# MicroMod-Ethernet-Function-Board-W5500.net
KiCad netlist of a schematic drawn in EAGLE
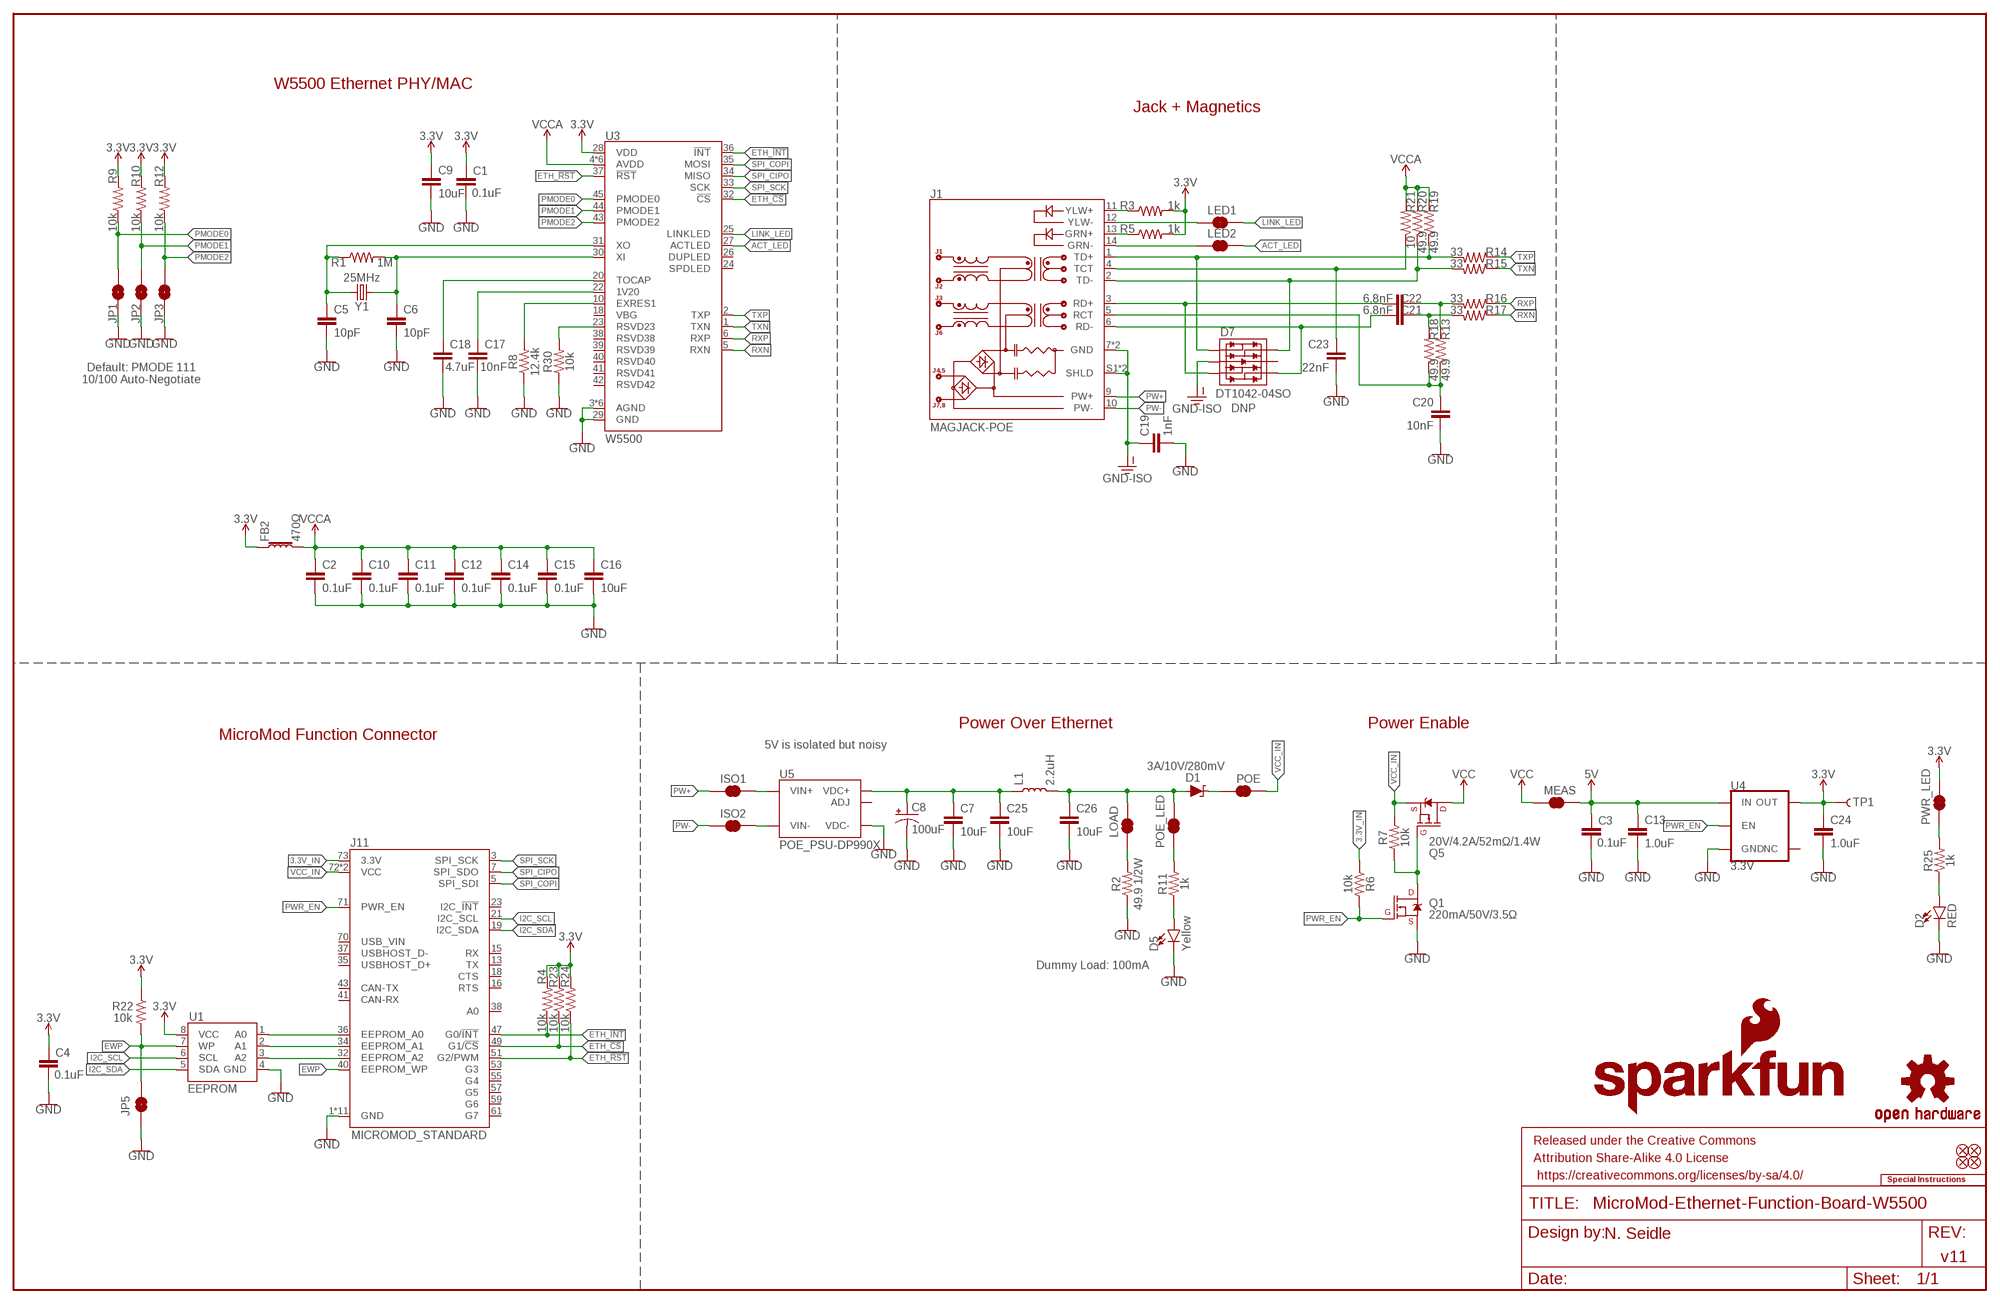
[diagram p0: schematic, sheet 1]

(export (version "E")
  (design (tool "Eeschema 10.0.6"))
  (components
    (comp (ref "C1")
      (value "0.1uF")
      (footprint "eagle-import:0603")
      (libsource (lib "eagle-import") (part "0.1UF-0603-25V-(+80/-20%)"))
    )
    (comp (ref "C2")
      (value "0.1uF")
      (footprint "eagle-import:0603")
      (libsource (lib "eagle-import") (part "0.1UF-0603-25V-5%"))
    )
    (comp (ref "C3")
      (value "0.1uF")
      (footprint "eagle-import:0603")
      (libsource (lib "eagle-import") (part "0.1UF-0603-25V-(+80/-20%)"))
    )
    (comp (ref "C4")
      (value "0.1uF")
      (footprint "eagle-import:0603")
      (libsource (lib "eagle-import") (part "0.1UF-0603-25V-(+80/-20%)"))
    )
    (comp (ref "C5")
      (value "10pF")
      (footprint "eagle-import:0603")
      (libsource (lib "eagle-import") (part "10PF-0603-50V-5%"))
    )
    (comp (ref "C6")
      (value "10pF")
      (footprint "eagle-import:0603")
      (libsource (lib "eagle-import") (part "10PF-0603-50V-5%"))
    )
    (comp (ref "C7")
      (value "10uF")
      (footprint "eagle-import:0805")
      (libsource (lib "eagle-import") (part "10UF-0805-25V-10%"))
    )
    (comp (ref "C8")
      (value "100uF")
      (footprint "eagle-import:PANASONIC_D")
      (libsource (lib "eagle-import") (part "100UF-POLAR-25V-20%(ELEC)"))
    )
    (comp (ref "C9")
      (value "10uF")
      (footprint "eagle-import:0603")
      (libsource (lib "eagle-import") (part "10UF-0603-6.3V-20%"))
    )
    (comp (ref "C10")
      (value "0.1uF")
      (footprint "eagle-import:0603")
      (libsource (lib "eagle-import") (part "0.1UF-0603-25V-5%"))
    )
    (comp (ref "C11")
      (value "0.1uF")
      (footprint "eagle-import:0603")
      (libsource (lib "eagle-import") (part "0.1UF-0603-25V-5%"))
    )
    (comp (ref "C12")
      (value "0.1uF")
      (footprint "eagle-import:0603")
      (libsource (lib "eagle-import") (part "0.1UF-0603-25V-5%"))
    )
    (comp (ref "C13")
      (value "1.0uF")
      (footprint "eagle-import:0603")
      (libsource (lib "eagle-import") (part "1.0UF-0603-16V-10%"))
    )
    (comp (ref "C14")
      (value "0.1uF")
      (footprint "eagle-import:0603")
      (libsource (lib "eagle-import") (part "0.1UF-0603-25V-5%"))
    )
    (comp (ref "C15")
      (value "0.1uF")
      (footprint "eagle-import:0603")
      (libsource (lib "eagle-import") (part "0.1UF-0603-25V-5%"))
    )
    (comp (ref "C16")
      (value "10uF")
      (footprint "eagle-import:0603")
      (libsource (lib "eagle-import") (part "10UF-0603-6.3V-20%"))
    )
    (comp (ref "C17")
      (value "10nF")
      (footprint "eagle-import:0603")
      (libsource (lib "eagle-import") (part "10NF-0603-50V-10%"))
    )
    (comp (ref "C18")
      (value "4.7uF")
      (footprint "eagle-import:0603")
      (libsource (lib "eagle-import") (part "4.7UF-0603-6.3V-(10%)"))
    )
    (comp (ref "C19")
      (value "1nF")
      (footprint "eagle-import:1206")
      (libsource (lib "eagle-import") (part "1.0NF/1000PF-1206-2KV-10%"))
    )
    (comp (ref "C20")
      (value "10nF")
      (footprint "eagle-import:0603")
      (libsource (lib "eagle-import") (part "10NF-0603-50V-10%"))
    )
    (comp (ref "C21")
      (value "6.8nF")
      (footprint "eagle-import:0603")
      (libsource (lib "eagle-import") (part "6.8NF/6800PF-0603-50V-5%"))
    )
    (comp (ref "C22")
      (value "6.8nF")
      (footprint "eagle-import:0603")
      (libsource (lib "eagle-import") (part "6.8NF/6800PF-0603-50V-5%"))
    )
    (comp (ref "C23")
      (value "22nF")
      (footprint "eagle-import:0603")
      (libsource (lib "eagle-import") (part "22NF/22,000PF-0603-50V-10%"))
    )
    (comp (ref "C24")
      (value "1.0uF")
      (footprint "eagle-import:0603")
      (libsource (lib "eagle-import") (part "1.0UF-0603-16V-10%-X7R"))
    )
    (comp (ref "C25")
      (value "10uF")
      (footprint "eagle-import:0805")
      (libsource (lib "eagle-import") (part "10UF-0805-25V-10%"))
    )
    (comp (ref "C26")
      (value "10uF")
      (footprint "eagle-import:0805")
      (libsource (lib "eagle-import") (part "10UF-0805-25V-10%"))
    )
    (comp (ref "D1")
      (value "3A/10V/280mV")
      (footprint "eagle-import:SOD-323")
      (libsource (lib "eagle-import") (part "DIODE-SCHOTTKY-BAT60A"))
    )
    (comp (ref "D2")
      (value "RED")
      (footprint "eagle-import:LED-0603")
      (libsource (lib "eagle-import") (part "LED-RED0603"))
    )
    (comp (ref "D5")
      (value "Yellow")
      (footprint "eagle-import:LED-0603")
      (libsource (lib "eagle-import") (part "LED-YELLOW0603"))
    )
    (comp (ref "D7")
      (value "DT1042-04SO")
      (footprint "eagle-import:SOT-23-6")
      (libsource (lib "eagle-import") (part "TVS_DIODE_ARRAYSMD"))
    )
    (comp (ref "FB2")
      (value "470Ω")
      (footprint "eagle-import:0603")
      (libsource (lib "eagle-import") (part "FERRITE_BEAD-0603-470Ω-100MHZ-1A-200MILIΩ"))
    )
    (comp (ref "FD1")
      (value "FIDUCIALUFIDUCIAL")
      (footprint "eagle-import:FIDUCIAL-MICRO")
      (libsource (lib "eagle-import") (part "FIDUCIALUFIDUCIAL"))
    )
    (comp (ref "FD2")
      (value "FIDUCIALUFIDUCIAL")
      (footprint "eagle-import:FIDUCIAL-MICRO")
      (libsource (lib "eagle-import") (part "FIDUCIALUFIDUCIAL"))
    )
    (comp (ref "FD3")
      (value "FIDUCIALUFIDUCIAL")
      (footprint "eagle-import:FIDUCIAL-MICRO")
      (libsource (lib "eagle-import") (part "FIDUCIALUFIDUCIAL"))
    )
    (comp (ref "FD4")
      (value "FIDUCIALUFIDUCIAL")
      (footprint "eagle-import:FIDUCIAL-MICRO")
      (libsource (lib "eagle-import") (part "FIDUCIALUFIDUCIAL"))
    )
    (comp (ref "FRAME1")
      (value "FRAME-LEDGER")
      (footprint "eagle-import:CREATIVE_COMMONS")
      (libsource (lib "eagle-import") (part "FRAME-LEDGER"))
    )
    (comp (ref "ISO1")
      (value "JUMPER-COMBO_2_NC_TRACE")
      (footprint "eagle-import:COMBO-JUMPER_2_NC_TRACE")
      (libsource (lib "eagle-import") (part "JUMPER-COMBO_2_NC_TRACE"))
    )
    (comp (ref "ISO2")
      (value "JUMPER-COMBO_2_NC_TRACE")
      (footprint "eagle-import:COMBO-JUMPER_2_NC_TRACE")
      (libsource (lib "eagle-import") (part "JUMPER-COMBO_2_NC_TRACE"))
    )
    (comp (ref "J1")
      (value "MAGJACK-POE")
      (footprint "eagle-import:MAGJACK-SYM_LED")
      (libsource (lib "eagle-import") (part "MAGJACK-POE"))
    )
    (comp (ref "J11")
      (value "MICROMOD_STANDARD")
      (footprint "eagle-import:M.2-CARD-E-22_FUNCTION_STANDARD")
      (libsource (lib "eagle-import") (part "MICROMOD_STANDARD"))
    )
    (comp (ref "JP1")
      (value "JUMPER-SMT_2_NO_SILK")
      (footprint "eagle-import:SMT-JUMPER_2_NO_SILK")
      (libsource (lib "eagle-import") (part "JUMPER-SMT_2_NO_SILK"))
    )
    (comp (ref "JP2")
      (value "JUMPER-SMT_2_NO_SILK")
      (footprint "eagle-import:SMT-JUMPER_2_NO_SILK")
      (libsource (lib "eagle-import") (part "JUMPER-SMT_2_NO_SILK"))
    )
    (comp (ref "JP3")
      (value "JUMPER-SMT_2_NO_SILK")
      (footprint "eagle-import:SMT-JUMPER_2_NO_SILK")
      (libsource (lib "eagle-import") (part "JUMPER-SMT_2_NO_SILK"))
    )
    (comp (ref "JP5")
      (value "JUMPER-SMT_2_NO_SILK")
      (footprint "eagle-import:SMT-JUMPER_2_NO_SILK")
      (libsource (lib "eagle-import") (part "JUMPER-SMT_2_NO_SILK"))
    )
    (comp (ref "L1")
      (value "2.2uH")
      (footprint "eagle-import:0805-WIDE")
      (libsource (lib "eagle-import") (part "INDUCTOR-0805_WIDE-2.2UH"))
    )
    (comp (ref "LED1")
      (value "JUMPER-SMT_2_NC_TRACE_SILK")
      (footprint "eagle-import:SMT-JUMPER_2_NC_TRACE_SILK")
      (libsource (lib "eagle-import") (part "JUMPER-SMT_2_NC_TRACE_SILK"))
    )
    (comp (ref "LED2")
      (value "JUMPER-SMT_2_NC_TRACE_SILK")
      (footprint "eagle-import:SMT-JUMPER_2_NC_TRACE_SILK")
      (libsource (lib "eagle-import") (part "JUMPER-SMT_2_NC_TRACE_SILK"))
    )
    (comp (ref "LOAD")
      (value "JUMPER-SMT_2_NC_TRACE_SILK")
      (footprint "eagle-import:SMT-JUMPER_2_NC_TRACE_SILK")
      (libsource (lib "eagle-import") (part "JUMPER-SMT_2_NC_TRACE_SILK"))
    )
    (comp (ref "LOGO1")
      (value "SFE_LOGO_NAME_FLAME.1_INCH")
      (footprint "eagle-import:SFE_LOGO_NAME_FLAME_.1")
      (libsource (lib "eagle-import") (part "SFE_LOGO_NAME_FLAME.1_INCH"))
    )
    (comp (ref "LOGO2")
      (value "SPECIAL_INSTRUCTIONS-ORDERING")
      (footprint "eagle-import:ORDERING_INSTRUCTIONS")
      (libsource (lib "eagle-import") (part "SPECIAL_INSTRUCTIONS-ORDERING"))
    )
    (comp (ref "LOGO3")
      (value "OSHW-LOGOMINI")
      (footprint "eagle-import:OSHW-LOGO-MINI")
      (libsource (lib "eagle-import") (part "OSHW-LOGOMINI"))
    )
    (comp (ref "MEAS")
      (value "JUMPER-COMBO_2_NC_TRACE")
      (footprint "eagle-import:COMBO-JUMPER_2_NC_TRACE")
      (libsource (lib "eagle-import") (part "JUMPER-COMBO_2_NC_TRACE"))
    )
    (comp (ref "POE")
      (value "JUMPER-SMT_2_NC_TRACE_SILK")
      (footprint "eagle-import:SMT-JUMPER_2_NC_TRACE_SILK")
      (libsource (lib "eagle-import") (part "JUMPER-SMT_2_NC_TRACE_SILK"))
    )
    (comp (ref "POE_LED")
      (value "JUMPER-SMT_2_NC_TRACE_SILK")
      (footprint "eagle-import:SMT-JUMPER_2_NC_TRACE_SILK")
      (libsource (lib "eagle-import") (part "JUMPER-SMT_2_NC_TRACE_SILK"))
    )
    (comp (ref "PWR_LED")
      (value "JUMPER-SMT_2_NC_TRACE_SILK")
      (footprint "eagle-import:SMT-JUMPER_2_NC_TRACE_SILK")
      (libsource (lib "eagle-import") (part "JUMPER-SMT_2_NC_TRACE_SILK"))
    )
    (comp (ref "Q1")
      (value "220mA/50V/3.5Ω")
      (footprint "eagle-import:SOT23-3")
      (libsource (lib "eagle-import") (part "MOSFET-NCH-BSS138"))
    )
    (comp (ref "Q5")
      (value "20V/4.2A/52mΩ/1.4W")
      (footprint "eagle-import:SOT23-3")
      (libsource (lib "eagle-import") (part "MOSFET_PCH-DMG2305UX-7"))
    )
    (comp (ref "R1")
      (value "1M")
      (footprint "eagle-import:0603")
      (libsource (lib "eagle-import") (part "1MOHM-0603-1/4W-5%"))
    )
    (comp (ref "R2")
      (value "49.9 1/2W")
      (footprint "eagle-import:1206")
      (libsource (lib "eagle-import") (part "49.9OHM-1206-1/2W-1%"))
    )
    (comp (ref "R3")
      (value "1k")
      (footprint "eagle-import:0603")
      (libsource (lib "eagle-import") (part "1KOHM-0603-1/10W-1%"))
    )
    (comp (ref "R4")
      (value "10k")
      (footprint "eagle-import:0603")
      (libsource (lib "eagle-import") (part "10KOHM-0603-1/10W-1%"))
    )
    (comp (ref "R5")
      (value "1k")
      (footprint "eagle-import:0603")
      (libsource (lib "eagle-import") (part "1KOHM-0603-1/10W-1%"))
    )
    (comp (ref "R6")
      (value "10k")
      (footprint "eagle-import:0603")
      (libsource (lib "eagle-import") (part "10KOHM-0603-1/10W-1%"))
    )
    (comp (ref "R7")
      (value "10k")
      (footprint "eagle-import:0603")
      (libsource (lib "eagle-import") (part "10KOHM-0603-1/10W-1%"))
    )
    (comp (ref "R8")
      (value "12.4k")
      (footprint "eagle-import:0603")
      (libsource (lib "eagle-import") (part "12.4KOHM-0603-1/10W-1%"))
    )
    (comp (ref "R9")
      (value "10k")
      (footprint "eagle-import:0603")
      (libsource (lib "eagle-import") (part "10KOHM-0603-1/10W-1%"))
    )
    (comp (ref "R10")
      (value "10k")
      (footprint "eagle-import:0603")
      (libsource (lib "eagle-import") (part "10KOHM-0603-1/10W-1%"))
    )
    (comp (ref "R11")
      (value "1k")
      (footprint "eagle-import:0603")
      (libsource (lib "eagle-import") (part "1KOHM-0603-1/10W-1%"))
    )
    (comp (ref "R12")
      (value "10k")
      (footprint "eagle-import:0603")
      (libsource (lib "eagle-import") (part "10KOHM-0603-1/10W-1%"))
    )
    (comp (ref "R13")
      (value "49.9")
      (footprint "eagle-import:0603")
      (libsource (lib "eagle-import") (part "49.9OHM-0603-1/10W-1%"))
    )
    (comp (ref "R14")
      (value "33")
      (footprint "eagle-import:0603")
      (libsource (lib "eagle-import") (part "33OHM-0603-1/10W-1%"))
    )
    (comp (ref "R15")
      (value "33")
      (footprint "eagle-import:0603")
      (libsource (lib "eagle-import") (part "33OHM-0603-1/10W-1%"))
    )
    (comp (ref "R16")
      (value "33")
      (footprint "eagle-import:0603")
      (libsource (lib "eagle-import") (part "33OHM-0603-1/10W-1%"))
    )
    (comp (ref "R17")
      (value "33")
      (footprint "eagle-import:0603")
      (libsource (lib "eagle-import") (part "33OHM-0603-1/10W-1%"))
    )
    (comp (ref "R18")
      (value "49.9")
      (footprint "eagle-import:0603")
      (libsource (lib "eagle-import") (part "49.9OHM-0603-1/10W-1%"))
    )
    (comp (ref "R19")
      (value "49.9")
      (footprint "eagle-import:0603")
      (libsource (lib "eagle-import") (part "49.9OHM-0603-1/10W-1%"))
    )
    (comp (ref "R20")
      (value "49.9")
      (footprint "eagle-import:0603")
      (libsource (lib "eagle-import") (part "49.9OHM-0603-1/10W-1%"))
    )
    (comp (ref "R21")
      (value "10")
      (footprint "eagle-import:0603")
      (libsource (lib "eagle-import") (part "10OHM-0603-1/10W-1%"))
    )
    (comp (ref "R22")
      (value "10k")
      (footprint "eagle-import:0603")
      (libsource (lib "eagle-import") (part "10KOHM-0603-1/10W-1%"))
    )
    (comp (ref "R23")
      (value "10k")
      (footprint "eagle-import:0603")
      (libsource (lib "eagle-import") (part "10KOHM-0603-1/10W-1%"))
    )
    (comp (ref "R24")
      (value "10k")
      (footprint "eagle-import:0603")
      (libsource (lib "eagle-import") (part "10KOHM-0603-1/10W-1%"))
    )
    (comp (ref "R25")
      (value "1k")
      (footprint "eagle-import:0603")
      (libsource (lib "eagle-import") (part "1KOHM-0603-1/10W-1%"))
    )
    (comp (ref "R30")
      (value "10k")
      (footprint "eagle-import:0603")
      (libsource (lib "eagle-import") (part "10KOHM-0603-1/10W-1%"))
    )
    (comp (ref "TP1")
      (value "TEST-POINT3X4")
      (footprint "eagle-import:PAD.03X.04")
      (libsource (lib "eagle-import") (part "TEST-POINT3X4"))
    )
    (comp (ref "U1")
      (value "EEPROM")
      (footprint "eagle-import:SO08")
      (libsource (lib "eagle-import") (part "EEPROM-I2C512K"))
    )
    (comp (ref "U3")
      (value "W5500")
      (footprint "eagle-import:LQFP-48")
      (libsource (lib "eagle-import") (part "W5500"))
    )
    (comp (ref "U4")
      (value "3.3V")
      (footprint "eagle-import:SOT23-5")
      (libsource (lib "eagle-import") (part "V_REG_AP2112K-3.3V"))
    )
    (comp (ref "U5")
      (value "POE_PSU-DP990X")
      (footprint "eagle-import:DP990X")
      (libsource (lib "eagle-import") (part "POE_PSU-DP990X"))
    )
    (comp (ref "Y1")
      (value "25MHz")
      (footprint "eagle-import:CRYSTAL-SMD-2.0X1.6MM")
      (libsource (lib "eagle-import") (part "CRYSTAL-25MHZ-SMD-2.0X1.6MM"))
    )
  )
  (nets
    (net (code "1") (name "/ETH_~{CS}") (class "Default")
      (node (ref "J11") (pin "49") (pinfunction "G1/~{CS}_49") (pintype "bidirectional"))
      (node (ref "R23") (pin "1") (pinfunction "1_1") (pintype "passive"))
      (node (ref "U3") (pin "32") (pinfunction "~{CS}_32") (pintype "bidirectional"))
    )
    (net (code "2") (name "/ETH_~{INT}") (class "Default")
      (node (ref "J11") (pin "47") (pinfunction "G0/~{INT}_47") (pintype "bidirectional"))
      (node (ref "R4") (pin "1") (pinfunction "1_1") (pintype "passive"))
      (node (ref "U3") (pin "36") (pinfunction "~{INT}_36") (pintype "bidirectional"))
    )
    (net (code "3") (name "/ETH_~{RST}") (class "Default")
      (node (ref "J11") (pin "51") (pinfunction "G2/PWM_51") (pintype "bidirectional"))
      (node (ref "R24") (pin "1") (pinfunction "1_1") (pintype "passive"))
      (node (ref "U3") (pin "37") (pinfunction "~{RST}_37") (pintype "bidirectional"))
    )
    (net (code "4") (name "3.3V") (class "Default")
      (node (ref "C1") (pin "1") (pinfunction "1_1") (pintype "passive"))
      (node (ref "C24") (pin "1") (pinfunction "1_1") (pintype "passive"))
      (node (ref "C4") (pin "1") (pinfunction "1_1") (pintype "passive"))
      (node (ref "C9") (pin "1") (pinfunction "1_1") (pintype "passive"))
      (node (ref "FB2") (pin "1") (pinfunction "1_1") (pintype "passive"))
      (node (ref "PWR_LED") (pin "2") (pinfunction "2_2") (pintype "passive"))
      (node (ref "R10") (pin "2") (pinfunction "2_2") (pintype "passive"))
      (node (ref "R12") (pin "2") (pinfunction "2_2") (pintype "passive"))
      (node (ref "R22") (pin "1") (pinfunction "1_1") (pintype "passive"))
      (node (ref "R23") (pin "2") (pinfunction "2_2") (pintype "passive"))
      (node (ref "R24") (pin "2") (pinfunction "2_2") (pintype "passive"))
      (node (ref "R3") (pin "2") (pinfunction "2_2") (pintype "passive"))
      (node (ref "R4") (pin "2") (pinfunction "2_2") (pintype "passive"))
      (node (ref "R5") (pin "2") (pinfunction "2_2") (pintype "passive"))
      (node (ref "R9") (pin "2") (pinfunction "2_2") (pintype "passive"))
      (node (ref "TP1") (pin "1") (pinfunction "1_1") (pintype "bidirectional"))
      (node (ref "U1") (pin "8") (pinfunction "VCC_8") (pintype "power_in"))
      (node (ref "U3") (pin "28") (pinfunction "VDD_28") (pintype "bidirectional"))
      (node (ref "U4") (pin "5") (pinfunction "OUT_5") (pintype "passive"))
    )
    (net (code "5") (name "3.3V_IN") (class "Default")
      (node (ref "J11") (pin "73") (pinfunction "3.3V_73") (pintype "bidirectional"))
      (node (ref "R6") (pin "1") (pinfunction "1_1") (pintype "passive"))
    )
    (net (code "6") (name "5V") (class "Default")
      (node (ref "C13") (pin "1") (pinfunction "1_1") (pintype "passive"))
      (node (ref "C3") (pin "1") (pinfunction "1_1") (pintype "passive"))
      (node (ref "MEAS") (pin "2") (pinfunction "2_2") (pintype "passive"))
      (node (ref "MEAS") (pin "4") (pinfunction "2_4") (pintype "passive"))
      (node (ref "U4") (pin "1") (pinfunction "IN_1") (pintype "input"))
    )
    (net (code "7") (name "ACT_LED") (class "Default")
      (node (ref "LED2") (pin "2") (pinfunction "2_2") (pintype "passive"))
      (node (ref "U3") (pin "27") (pinfunction "ACTLED_27") (pintype "bidirectional"))
    )
    (net (code "8") (name "EWP") (class "Default")
      (node (ref "J11") (pin "40") (pinfunction "EEPROM_WP_40") (pintype "bidirectional"))
      (node (ref "JP5") (pin "2") (pinfunction "2_2") (pintype "passive"))
      (node (ref "R22") (pin "2") (pinfunction "2_2") (pintype "passive"))
      (node (ref "U1") (pin "7") (pinfunction "WP_7") (pintype "bidirectional"))
    )
    (net (code "9") (name "GND") (class "Default")
      (node (ref "C1") (pin "2") (pinfunction "2_2") (pintype "passive"))
      (node (ref "C10") (pin "2") (pinfunction "2_2") (pintype "passive"))
      (node (ref "C11") (pin "2") (pinfunction "2_2") (pintype "passive"))
      (node (ref "C12") (pin "2") (pinfunction "2_2") (pintype "passive"))
      (node (ref "C13") (pin "2") (pinfunction "2_2") (pintype "passive"))
      (node (ref "C14") (pin "2") (pinfunction "2_2") (pintype "passive"))
      (node (ref "C15") (pin "2") (pinfunction "2_2") (pintype "passive"))
      (node (ref "C16") (pin "2") (pinfunction "2_2") (pintype "passive"))
      (node (ref "C17") (pin "2") (pinfunction "2_2") (pintype "passive"))
      (node (ref "C18") (pin "2") (pinfunction "2_2") (pintype "passive"))
      (node (ref "C19") (pin "2") (pinfunction "2_2") (pintype "passive"))
      (node (ref "C2") (pin "2") (pinfunction "2_2") (pintype "passive"))
      (node (ref "C20") (pin "2") (pinfunction "2_2") (pintype "passive"))
      (node (ref "C23") (pin "2") (pinfunction "2_2") (pintype "passive"))
      (node (ref "C24") (pin "2") (pinfunction "2_2") (pintype "passive"))
      (node (ref "C25") (pin "2") (pinfunction "2_2") (pintype "passive"))
      (node (ref "C26") (pin "2") (pinfunction "2_2") (pintype "passive"))
      (node (ref "C3") (pin "2") (pinfunction "2_2") (pintype "passive"))
      (node (ref "C4") (pin "2") (pinfunction "2_2") (pintype "passive"))
      (node (ref "C5") (pin "2") (pinfunction "2_2") (pintype "passive"))
      (node (ref "C6") (pin "2") (pinfunction "2_2") (pintype "passive"))
      (node (ref "C7") (pin "2") (pinfunction "2_2") (pintype "passive"))
      (node (ref "C8") (pin "-") (pinfunction "-_-") (pintype "passive"))
      (node (ref "C9") (pin "2") (pinfunction "2_2") (pintype "passive"))
      (node (ref "D2") (pin "C") (pinfunction "C_C") (pintype "passive"))
      (node (ref "D5") (pin "C") (pinfunction "C_C") (pintype "passive"))
      (node (ref "J11") (pin "1") (pinfunction "GND_1") (pintype "bidirectional"))
      (node (ref "J11") (pin "33") (pinfunction "GND_33") (pintype "bidirectional"))
      (node (ref "J11") (pin "39") (pinfunction "GND_39") (pintype "bidirectional"))
      (node (ref "J11") (pin "45") (pinfunction "GND_45") (pintype "bidirectional"))
      (node (ref "J11") (pin "75") (pinfunction "GND_75") (pintype "bidirectional"))
      (node (ref "J11") (pin "GND1") (pinfunction "GND_GND1") (pintype "bidirectional"))
      (node (ref "J11") (pin "GND2") (pinfunction "GND_GND2") (pintype "bidirectional"))
      (node (ref "J11") (pin "GND3") (pinfunction "GND_GND3") (pintype "bidirectional"))
      (node (ref "J11") (pin "GND4") (pinfunction "GND_GND4") (pintype "bidirectional"))
      (node (ref "J11") (pin "GND5") (pinfunction "GND_GND5") (pintype "bidirectional"))
      (node (ref "J11") (pin "GND6") (pinfunction "GND_GND6") (pintype "bidirectional"))
      (node (ref "JP1") (pin "1") (pinfunction "1_1") (pintype "passive"))
      (node (ref "JP2") (pin "1") (pinfunction "1_1") (pintype "passive"))
      (node (ref "JP3") (pin "1") (pinfunction "1_1") (pintype "passive"))
      (node (ref "JP5") (pin "1") (pinfunction "1_1") (pintype "passive"))
      (node (ref "Q1") (pin "2") (pinfunction "S_2") (pintype "bidirectional"))
      (node (ref "R2") (pin "1") (pinfunction "1_1") (pintype "passive"))
      (node (ref "R30") (pin "1") (pinfunction "1_1") (pintype "passive"))
      (node (ref "R8") (pin "1") (pinfunction "1_1") (pintype "passive"))
      (node (ref "U1") (pin "4") (pinfunction "GND_4") (pintype "power_in"))
      (node (ref "U3") (pin "14") (pinfunction "AGND_14") (pintype "bidirectional"))
      (node (ref "U3") (pin "16") (pinfunction "AGND_16") (pintype "bidirectional"))
      (node (ref "U3") (pin "19") (pinfunction "AGND_19") (pintype "bidirectional"))
      (node (ref "U3") (pin "29") (pinfunction "GND_29") (pintype "bidirectional"))
      (node (ref "U3") (pin "3") (pinfunction "AGND_3") (pintype "bidirectional"))
      (node (ref "U3") (pin "48") (pinfunction "AGND_48") (pintype "bidirectional"))
      (node (ref "U3") (pin "9") (pinfunction "AGND_9") (pintype "bidirectional"))
      (node (ref "U4") (pin "2") (pinfunction "GND_2") (pintype "input"))
      (node (ref "U5") (pin "3") (pinfunction "VDC-_3") (pintype "bidirectional"))
    )
    (net (code "10") (name "GND-ISO") (class "Default")
      (node (ref "C19") (pin "1") (pinfunction "1_1") (pintype "passive"))
      (node (ref "D7") (pin "2") (pinfunction "VSS_2") (pintype "bidirectional"))
      (node (ref "J1") (pin "7") (pinfunction "GND_7") (pintype "bidirectional"))
      (node (ref "J1") (pin "8") (pinfunction "GND_8") (pintype "bidirectional"))
      (node (ref "J1") (pin "S1") (pinfunction "SHLD_S1") (pintype "bidirectional"))
      (node (ref "J1") (pin "S2") (pinfunction "SHLD_S2") (pintype "bidirectional"))
    )
    (net (code "11") (name "I2C_SCL") (class "Default")
      (node (ref "J11") (pin "21") (pinfunction "I2C_SCL_21") (pintype "bidirectional"))
      (node (ref "U1") (pin "6") (pinfunction "SCL_6") (pintype "bidirectional"))
    )
    (net (code "12") (name "I2C_SDA") (class "Default")
      (node (ref "J11") (pin "19") (pinfunction "I2C_SDA_19") (pintype "bidirectional"))
      (node (ref "U1") (pin "5") (pinfunction "SDA_5") (pintype "bidirectional"))
    )
    (net (code "13") (name "LINK_LED") (class "Default")
      (node (ref "LED1") (pin "2") (pinfunction "2_2") (pintype "passive"))
      (node (ref "U3") (pin "25") (pinfunction "LINKLED_25") (pintype "bidirectional"))
    )
    (net (code "14") (name "Net-(C21-Pad1)") (class "Default")
      (node (ref "C21") (pin "1") (pinfunction "1_1") (pintype "passive"))
      (node (ref "R17") (pin "2") (pinfunction "2_2") (pintype "passive"))
      (node (ref "R18") (pin "2") (pinfunction "2_2") (pintype "passive"))
    )
    (net (code "15") (name "Net-(C22-Pad1)") (class "Default")
      (node (ref "C22") (pin "1") (pinfunction "1_1") (pintype "passive"))
      (node (ref "R13") (pin "2") (pinfunction "2_2") (pintype "passive"))
      (node (ref "R16") (pin "2") (pinfunction "2_2") (pintype "passive"))
    )
    (net (code "16") (name "Net-(C25-Pad1)") (class "Default")
      (node (ref "C25") (pin "1") (pinfunction "1_1") (pintype "passive"))
      (node (ref "C7") (pin "1") (pinfunction "1_1") (pintype "passive"))
      (node (ref "C8") (pin "+") (pinfunction "+_+") (pintype "passive"))
      (node (ref "L1") (pin "1") (pinfunction "1_1") (pintype "passive"))
      (node (ref "U5") (pin "1") (pinfunction "VDC+_1") (pintype "bidirectional"))
      (node (ref "U5") (pin "2") (pinfunction "VDC+_2") (pintype "bidirectional"))
    )
    (net (code "17") (name "Net-(C26-Pad1)") (class "Default")
      (node (ref "C26") (pin "1") (pinfunction "1_1") (pintype "passive"))
      (node (ref "D1") (pin "A") (pinfunction "A_A") (pintype "passive"))
      (node (ref "L1") (pin "2") (pinfunction "2_2") (pintype "passive"))
      (node (ref "LOAD") (pin "2") (pinfunction "2_2") (pintype "passive"))
      (node (ref "POE_LED") (pin "2") (pinfunction "2_2") (pintype "passive"))
    )
    (net (code "18") (name "Net-(D1-PadC)") (class "Default")
      (node (ref "D1") (pin "C") (pinfunction "C_C") (pintype "passive"))
      (node (ref "POE") (pin "1") (pinfunction "1_1") (pintype "passive"))
    )
    (net (code "19") (name "Net-(D2-PadA)") (class "Default")
      (node (ref "D2") (pin "A") (pinfunction "A_A") (pintype "passive"))
      (node (ref "R25") (pin "1") (pinfunction "1_1") (pintype "passive"))
    )
    (net (code "20") (name "Net-(D5-PadA)") (class "Default")
      (node (ref "D5") (pin "A") (pinfunction "A_A") (pintype "passive"))
      (node (ref "R11") (pin "1") (pinfunction "1_1") (pintype "passive"))
    )
    (net (code "21") (name "Net-(D7-IO1)") (class "Default")
      (node (ref "D7") (pin "1") (pinfunction "IO1_1") (pintype "bidirectional"))
      (node (ref "J1") (pin "1") (pinfunction "TD+_1") (pintype "bidirectional"))
      (node (ref "R14") (pin "2") (pinfunction "2_2") (pintype "passive"))
      (node (ref "R19") (pin "1") (pinfunction "1_1") (pintype "passive"))
    )
    (net (code "22") (name "Net-(D7-IO2)") (class "Default")
      (node (ref "C22") (pin "2") (pinfunction "2_2") (pintype "passive"))
      (node (ref "D7") (pin "3") (pinfunction "IO2_3") (pintype "bidirectional"))
      (node (ref "J1") (pin "3") (pinfunction "RD+_3") (pintype "bidirectional"))
    )
    (net (code "23") (name "Net-(D7-IO3)") (class "Default")
      (node (ref "C21") (pin "2") (pinfunction "2_2") (pintype "passive"))
      (node (ref "D7") (pin "4") (pinfunction "IO3_4") (pintype "bidirectional"))
      (node (ref "J1") (pin "6") (pinfunction "RD-_6") (pintype "bidirectional"))
    )
    (net (code "24") (name "Net-(D7-IO4)") (class "Default")
      (node (ref "D7") (pin "6") (pinfunction "IO4_6") (pintype "bidirectional"))
      (node (ref "J1") (pin "2") (pinfunction "TD-_2") (pintype "bidirectional"))
      (node (ref "R15") (pin "2") (pinfunction "2_2") (pintype "passive"))
      (node (ref "R20") (pin "1") (pinfunction "1_1") (pintype "passive"))
    )
    (net (code "25") (name "Net-(ISO1-2-Pad4)") (class "Default")
      (node (ref "ISO1") (pin "2") (pinfunction "2_2") (pintype "passive"))
      (node (ref "ISO1") (pin "4") (pinfunction "2_4") (pintype "passive"))
      (node (ref "U5") (pin "5") (pinfunction "VIN+_5") (pintype "bidirectional"))
      (node (ref "U5") (pin "6") (pinfunction "VIN+_6") (pintype "bidirectional"))
    )
    (net (code "26") (name "Net-(ISO2-2-Pad4)") (class "Default")
      (node (ref "ISO2") (pin "2") (pinfunction "2_2") (pintype "passive"))
      (node (ref "ISO2") (pin "4") (pinfunction "2_4") (pintype "passive"))
      (node (ref "U5") (pin "7") (pinfunction "VIN-_7") (pintype "bidirectional"))
      (node (ref "U5") (pin "8") (pinfunction "VIN-_8") (pintype "bidirectional"))
    )
    (net (code "27") (name "Net-(J1-GRN+)") (class "Default")
      (node (ref "J1") (pin "13") (pinfunction "GRN+_13") (pintype "bidirectional"))
      (node (ref "R5") (pin "1") (pinfunction "1_1") (pintype "passive"))
    )
    (net (code "28") (name "Net-(J1-GRN-)") (class "Default")
      (node (ref "J1") (pin "14") (pinfunction "GRN-_14") (pintype "bidirectional"))
      (node (ref "LED2") (pin "1") (pinfunction "1_1") (pintype "passive"))
    )
    (net (code "29") (name "Net-(J1-RCT)") (class "Default")
      (node (ref "C20") (pin "1") (pinfunction "1_1") (pintype "passive"))
      (node (ref "J1") (pin "5") (pinfunction "RCT_5") (pintype "bidirectional"))
      (node (ref "R13") (pin "1") (pinfunction "1_1") (pintype "passive"))
      (node (ref "R18") (pin "1") (pinfunction "1_1") (pintype "passive"))
    )
    (net (code "30") (name "Net-(J1-TCT)") (class "Default")
      (node (ref "C23") (pin "1") (pinfunction "1_1") (pintype "passive"))
      (node (ref "J1") (pin "4") (pinfunction "TCT_4") (pintype "bidirectional"))
      (node (ref "R21") (pin "1") (pinfunction "1_1") (pintype "passive"))
    )
    (net (code "31") (name "Net-(J1-YLW+)") (class "Default")
      (node (ref "J1") (pin "11") (pinfunction "YLW+_11") (pintype "bidirectional"))
      (node (ref "R3") (pin "1") (pinfunction "1_1") (pintype "passive"))
    )
    (net (code "32") (name "Net-(J1-YLW-)") (class "Default")
      (node (ref "J1") (pin "12") (pinfunction "YLW-_12") (pintype "bidirectional"))
      (node (ref "LED1") (pin "1") (pinfunction "1_1") (pintype "passive"))
    )
    (net (code "33") (name "Net-(J11-EEPROM_A0)") (class "Default")
      (node (ref "J11") (pin "36") (pinfunction "EEPROM_A0_36") (pintype "bidirectional"))
      (node (ref "U1") (pin "1") (pinfunction "A0_1") (pintype "bidirectional"))
    )
    (net (code "34") (name "Net-(J11-EEPROM_A1)") (class "Default")
      (node (ref "J11") (pin "34") (pinfunction "EEPROM_A1_34") (pintype "bidirectional"))
      (node (ref "U1") (pin "2") (pinfunction "A1_2") (pintype "bidirectional"))
    )
    (net (code "35") (name "Net-(J11-EEPROM_A2)") (class "Default")
      (node (ref "J11") (pin "32") (pinfunction "EEPROM_A2_32") (pintype "bidirectional"))
      (node (ref "U1") (pin "3") (pinfunction "A2_3") (pintype "bidirectional"))
    )
    (net (code "36") (name "Net-(LOAD-Pad1)") (class "Default")
      (node (ref "LOAD") (pin "1") (pinfunction "1_1") (pintype "passive"))
      (node (ref "R2") (pin "2") (pinfunction "2_2") (pintype "passive"))
    )
    (net (code "37") (name "Net-(POE_LED-Pad1)") (class "Default")
      (node (ref "POE_LED") (pin "1") (pinfunction "1_1") (pintype "passive"))
      (node (ref "R11") (pin "2") (pinfunction "2_2") (pintype "passive"))
    )
    (net (code "38") (name "Net-(PWR_LED-Pad1)") (class "Default")
      (node (ref "PWR_LED") (pin "1") (pinfunction "1_1") (pintype "passive"))
      (node (ref "R25") (pin "2") (pinfunction "2_2") (pintype "passive"))
    )
    (net (code "39") (name "Net-(Q1-D)") (class "Default")
      (node (ref "Q1") (pin "3") (pinfunction "D_3") (pintype "bidirectional"))
      (node (ref "Q5") (pin "1") (pinfunction "G_1") (pintype "bidirectional"))
      (node (ref "R7") (pin "1") (pinfunction "1_1") (pintype "passive"))
    )
    (net (code "40") (name "Net-(U3-1V20)") (class "Default")
      (node (ref "C17") (pin "1") (pinfunction "1_1") (pintype "passive"))
      (node (ref "U3") (pin "22") (pinfunction "1V20_22") (pintype "bidirectional"))
    )
    (net (code "41") (name "Net-(U3-EXRES1)") (class "Default")
      (node (ref "R8") (pin "2") (pinfunction "2_2") (pintype "passive"))
      (node (ref "U3") (pin "10") (pinfunction "EXRES1_10") (pintype "bidirectional"))
    )
    (net (code "42") (name "Net-(U3-RSVD23)") (class "Default")
      (node (ref "R30") (pin "2") (pinfunction "2_2") (pintype "passive"))
      (node (ref "U3") (pin "23") (pinfunction "RSVD23_23") (pintype "bidirectional"))
    )
    (net (code "43") (name "Net-(U3-TOCAP)") (class "Default")
      (node (ref "C18") (pin "1") (pinfunction "1_1") (pintype "passive"))
      (node (ref "U3") (pin "20") (pinfunction "TOCAP_20") (pintype "bidirectional"))
    )
    (net (code "44") (name "Net-(U3-XI)") (class "Default")
      (node (ref "C6") (pin "1") (pinfunction "1_1") (pintype "passive"))
      (node (ref "R1") (pin "2") (pinfunction "2_2") (pintype "passive"))
      (node (ref "U3") (pin "30") (pinfunction "XI_30") (pintype "bidirectional"))
      (node (ref "Y1") (pin "3") (pinfunction "2_3") (pintype "passive"))
    )
    (net (code "45") (name "Net-(U3-XO)") (class "Default")
      (node (ref "C5") (pin "1") (pinfunction "1_1") (pintype "passive"))
      (node (ref "R1") (pin "1") (pinfunction "1_1") (pintype "passive"))
      (node (ref "U3") (pin "31") (pinfunction "XO_31") (pintype "bidirectional"))
      (node (ref "Y1") (pin "1") (pinfunction "1_1") (pintype "passive"))
    )
    (net (code "46") (name "PMODE0") (class "Default")
      (node (ref "JP1") (pin "2") (pinfunction "2_2") (pintype "passive"))
      (node (ref "R9") (pin "1") (pinfunction "1_1") (pintype "passive"))
      (node (ref "U3") (pin "45") (pinfunction "PMODE0_45") (pintype "bidirectional"))
    )
    (net (code "47") (name "PMODE1") (class "Default")
      (node (ref "JP2") (pin "2") (pinfunction "2_2") (pintype "passive"))
      (node (ref "R10") (pin "1") (pinfunction "1_1") (pintype "passive"))
      (node (ref "U3") (pin "44") (pinfunction "PMODE1_44") (pintype "bidirectional"))
    )
    (net (code "48") (name "PMODE2") (class "Default")
      (node (ref "JP3") (pin "2") (pinfunction "2_2") (pintype "passive"))
      (node (ref "R12") (pin "1") (pinfunction "1_1") (pintype "passive"))
      (node (ref "U3") (pin "43") (pinfunction "PMODE2_43") (pintype "bidirectional"))
    )
    (net (code "49") (name "PW+") (class "Default")
      (node (ref "ISO1") (pin "1") (pinfunction "1_1") (pintype "passive"))
      (node (ref "ISO1") (pin "3") (pinfunction "1_3") (pintype "passive"))
      (node (ref "J1") (pin "9") (pinfunction "PW+_9") (pintype "bidirectional"))
    )
    (net (code "50") (name "PW-") (class "Default")
      (node (ref "ISO2") (pin "1") (pinfunction "1_1") (pintype "passive"))
      (node (ref "ISO2") (pin "3") (pinfunction "1_3") (pintype "passive"))
      (node (ref "J1") (pin "10") (pinfunction "PW-_10") (pintype "bidirectional"))
    )
    (net (code "51") (name "PWR_EN") (class "Default")
      (node (ref "J11") (pin "71") (pinfunction "PWR_EN_71") (pintype "bidirectional"))
      (node (ref "Q1") (pin "1") (pinfunction "G_1") (pintype "bidirectional"))
      (node (ref "R6") (pin "2") (pinfunction "2_2") (pintype "passive"))
      (node (ref "U4") (pin "3") (pinfunction "EN_3") (pintype "input"))
    )
    (net (code "52") (name "RXN") (class "Default")
      (node (ref "R17") (pin "1") (pinfunction "1_1") (pintype "passive"))
      (node (ref "U3") (pin "5") (pinfunction "RXN_5") (pintype "bidirectional"))
    )
    (net (code "53") (name "RXP") (class "Default")
      (node (ref "R16") (pin "1") (pinfunction "1_1") (pintype "passive"))
      (node (ref "U3") (pin "6") (pinfunction "RXP_6") (pintype "bidirectional"))
    )
    (net (code "54") (name "SPI_CIPO") (class "Default")
      (node (ref "J11") (pin "7") (pinfunction "SPI_SDO_7") (pintype "bidirectional"))
      (node (ref "U3") (pin "34") (pinfunction "MISO_34") (pintype "bidirectional"))
    )
    (net (code "55") (name "SPI_COPI") (class "Default")
      (node (ref "J11") (pin "5") (pinfunction "SPI_SDI_5") (pintype "bidirectional"))
      (node (ref "U3") (pin "35") (pinfunction "MOSI_35") (pintype "bidirectional"))
    )
    (net (code "56") (name "SPI_SCK") (class "Default")
      (node (ref "J11") (pin "3") (pinfunction "SPI_SCK_3") (pintype "bidirectional"))
      (node (ref "U3") (pin "33") (pinfunction "SCK_33") (pintype "bidirectional"))
    )
    (net (code "57") (name "TXN") (class "Default")
      (node (ref "R15") (pin "1") (pinfunction "1_1") (pintype "passive"))
      (node (ref "U3") (pin "1") (pinfunction "TXN_1") (pintype "bidirectional"))
    )
    (net (code "58") (name "TXP") (class "Default")
      (node (ref "R14") (pin "1") (pinfunction "1_1") (pintype "passive"))
      (node (ref "U3") (pin "2") (pinfunction "TXP_2") (pintype "bidirectional"))
    )
    (net (code "59") (name "VCC") (class "Default")
      (node (ref "MEAS") (pin "1") (pinfunction "1_1") (pintype "passive"))
      (node (ref "MEAS") (pin "3") (pinfunction "1_3") (pintype "passive"))
      (node (ref "Q5") (pin "3") (pinfunction "D_3") (pintype "bidirectional"))
    )
    (net (code "60") (name "VCCA") (class "Default")
      (node (ref "C10") (pin "1") (pinfunction "1_1") (pintype "passive"))
      (node (ref "C11") (pin "1") (pinfunction "1_1") (pintype "passive"))
      (node (ref "C12") (pin "1") (pinfunction "1_1") (pintype "passive"))
      (node (ref "C14") (pin "1") (pinfunction "1_1") (pintype "passive"))
      (node (ref "C15") (pin "1") (pinfunction "1_1") (pintype "passive"))
      (node (ref "C16") (pin "1") (pinfunction "1_1") (pintype "passive"))
      (node (ref "C2") (pin "1") (pinfunction "1_1") (pintype "passive"))
      (node (ref "FB2") (pin "2") (pinfunction "2_2") (pintype "passive"))
      (node (ref "R19") (pin "2") (pinfunction "2_2") (pintype "passive"))
      (node (ref "R20") (pin "2") (pinfunction "2_2") (pintype "passive"))
      (node (ref "R21") (pin "2") (pinfunction "2_2") (pintype "passive"))
      (node (ref "U3") (pin "11") (pinfunction "AVDD_11") (pintype "bidirectional"))
      (node (ref "U3") (pin "15") (pinfunction "AVDD_15") (pintype "bidirectional"))
      (node (ref "U3") (pin "17") (pinfunction "AVDD_17") (pintype "bidirectional"))
      (node (ref "U3") (pin "21") (pinfunction "AVDD_21") (pintype "bidirectional"))
      (node (ref "U3") (pin "4") (pinfunction "AVDD_4") (pintype "bidirectional"))
      (node (ref "U3") (pin "8") (pinfunction "AVDD_8") (pintype "bidirectional"))
    )
    (net (code "61") (name "VCC_IN") (class "Default")
      (node (ref "J11") (pin "72") (pinfunction "VCC_72") (pintype "bidirectional"))
      (node (ref "J11") (pin "74") (pinfunction "VCC_74") (pintype "bidirectional"))
      (node (ref "POE") (pin "2") (pinfunction "2_2") (pintype "passive"))
      (node (ref "Q5") (pin "2") (pinfunction "S_2") (pintype "bidirectional"))
      (node (ref "R7") (pin "2") (pinfunction "2_2") (pintype "passive"))
    )
    (net (code "62") (name "unconnected-(D7-VCC-Pad5)") (class "Default")
      (node (ref "D7") (pin "5") (pinfunction "VCC_5") (pintype "bidirectional"))
    )
    (net (code "63") (name "unconnected-(J11-A0-Pad38)") (class "Default")
      (node (ref "J11") (pin "38") (pinfunction "A0_38") (pintype "bidirectional"))
    )
    (net (code "64") (name "unconnected-(J11-CAN-RX-Pad41)") (class "Default")
      (node (ref "J11") (pin "41") (pinfunction "CAN-RX_41") (pintype "bidirectional"))
    )
    (net (code "65") (name "unconnected-(J11-CAN-TX-Pad43)") (class "Default")
      (node (ref "J11") (pin "43") (pinfunction "CAN-TX_43") (pintype "bidirectional"))
    )
    (net (code "66") (name "unconnected-(J11-CTS-Pad18)") (class "Default")
      (node (ref "J11") (pin "18") (pinfunction "CTS_18") (pintype "bidirectional"))
    )
    (net (code "67") (name "unconnected-(J11-G3-Pad53)") (class "Default")
      (node (ref "J11") (pin "53") (pinfunction "G3_53") (pintype "bidirectional"))
    )
    (net (code "68") (name "unconnected-(J11-G4-Pad55)") (class "Default")
      (node (ref "J11") (pin "55") (pinfunction "G4_55") (pintype "bidirectional"))
    )
    (net (code "69") (name "unconnected-(J11-G5-Pad57)") (class "Default")
      (node (ref "J11") (pin "57") (pinfunction "G5_57") (pintype "bidirectional"))
    )
    (net (code "70") (name "unconnected-(J11-G6-Pad59)") (class "Default")
      (node (ref "J11") (pin "59") (pinfunction "G6_59") (pintype "bidirectional"))
    )
    (net (code "71") (name "unconnected-(J11-G7-Pad61)") (class "Default")
      (node (ref "J11") (pin "61") (pinfunction "G7_61") (pintype "bidirectional"))
    )
    (net (code "72") (name "unconnected-(J11-I2C_~{INT}-Pad23)") (class "Default")
      (node (ref "J11") (pin "23") (pinfunction "I2C_~{INT}_23") (pintype "bidirectional"))
    )
    (net (code "73") (name "unconnected-(J11-RTS-Pad16)") (class "Default")
      (node (ref "J11") (pin "16") (pinfunction "RTS_16") (pintype "bidirectional"))
    )
    (net (code "74") (name "unconnected-(J11-RX-Pad15)") (class "Default")
      (node (ref "J11") (pin "15") (pinfunction "RX_15") (pintype "bidirectional"))
    )
    (net (code "75") (name "unconnected-(J11-TX-Pad13)") (class "Default")
      (node (ref "J11") (pin "13") (pinfunction "TX_13") (pintype "bidirectional"))
    )
    (net (code "76") (name "unconnected-(J11-USBHOST_D+-Pad35)") (class "Default")
      (node (ref "J11") (pin "35") (pinfunction "USBHOST_D+_35") (pintype "bidirectional"))
    )
    (net (code "77") (name "unconnected-(J11-USBHOST_D--Pad37)") (class "Default")
      (node (ref "J11") (pin "37") (pinfunction "USBHOST_D-_37") (pintype "bidirectional"))
    )
    (net (code "78") (name "unconnected-(J11-USB_VIN-Pad70)") (class "Default")
      (node (ref "J11") (pin "70") (pinfunction "USB_VIN_70") (pintype "bidirectional"))
    )
    (net (code "79") (name "unconnected-(U3-DUPLED-Pad26)") (class "Default")
      (node (ref "U3") (pin "26") (pinfunction "DUPLED_26") (pintype "bidirectional"))
    )
    (net (code "80") (name "unconnected-(U3-RSVD38-Pad38)") (class "Default")
      (node (ref "U3") (pin "38") (pinfunction "RSVD38_38") (pintype "bidirectional"))
    )
    (net (code "81") (name "unconnected-(U3-RSVD39-Pad39)") (class "Default")
      (node (ref "U3") (pin "39") (pinfunction "RSVD39_39") (pintype "bidirectional"))
    )
    (net (code "82") (name "unconnected-(U3-RSVD40-Pad40)") (class "Default")
      (node (ref "U3") (pin "40") (pinfunction "RSVD40_40") (pintype "bidirectional"))
    )
    (net (code "83") (name "unconnected-(U3-RSVD41-Pad41)") (class "Default")
      (node (ref "U3") (pin "41") (pinfunction "RSVD41_41") (pintype "bidirectional"))
    )
    (net (code "84") (name "unconnected-(U3-RSVD42-Pad42)") (class "Default")
      (node (ref "U3") (pin "42") (pinfunction "RSVD42_42") (pintype "bidirectional"))
    )
    (net (code "85") (name "unconnected-(U3-SPDLED-Pad24)") (class "Default")
      (node (ref "U3") (pin "24") (pinfunction "SPDLED_24") (pintype "bidirectional"))
    )
    (net (code "86") (name "unconnected-(U3-VBG-Pad18)") (class "Default")
      (node (ref "U3") (pin "18") (pinfunction "VBG_18") (pintype "bidirectional"))
    )
    (net (code "87") (name "unconnected-(U4-NC-Pad4)") (class "Default")
      (node (ref "U4") (pin "4") (pinfunction "NC_4") (pintype "no_connect"))
    )
    (net (code "88") (name "unconnected-(U5-ADJ-Pad4)") (class "Default")
      (node (ref "U5") (pin "4") (pinfunction "ADJ_4") (pintype "bidirectional"))
    )
  )
)
